# iPod-Video-breakout.net
KiCad netlist of a schematic drawn in EAGLE
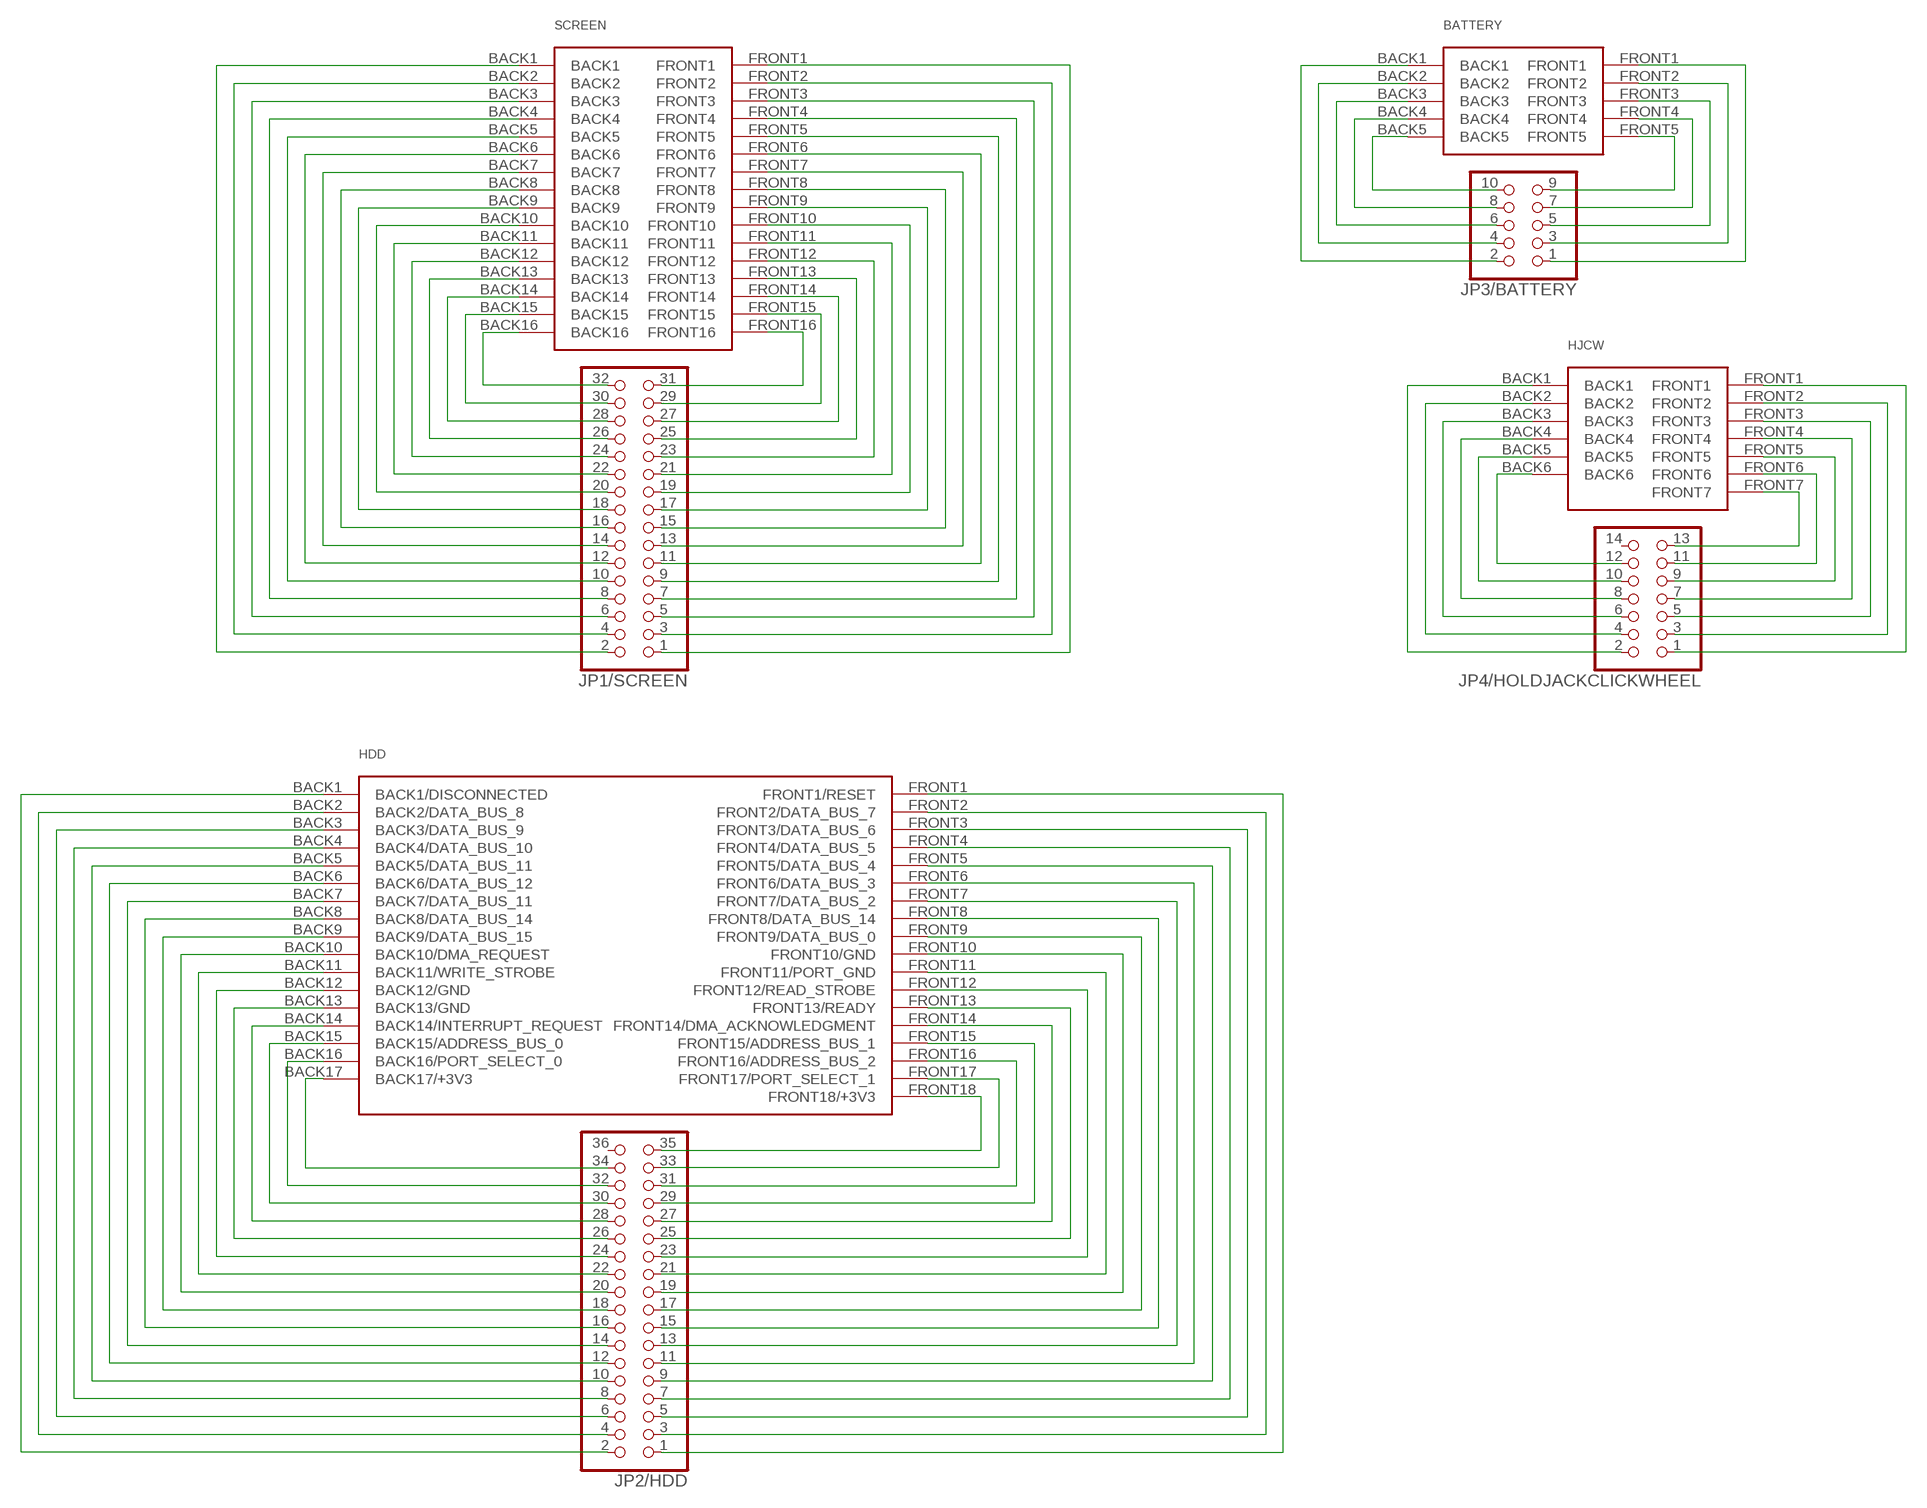
[diagram p0: schematic, sheet 1]

(export (version "E")
  (design (tool "Eeschema 10.0.6"))
  (components
    (comp (ref "BATTERY")
      (value "526100572/BATTERY")
      (footprint "eagle-import:526100572")
      (libsource (lib "eagle-import") (part "526100572/BATTERY"))
    )
    (comp (ref "HDD")
      (value "5035663502/HDD")
      (footprint "eagle-import:5035663502")
      (libsource (lib "eagle-import") (part "5035663502/HDD"))
    )
    (comp (ref "HJCW")
      (value "5035661302/HOLDJACK&CLICKWHEEL")
      (footprint "eagle-import:5035661302")
      (libsource (lib "eagle-import") (part "5035661302/HOLDJACK&CLICKWHEEL"))
    )
    (comp (ref "JP1/SCREEN")
      (value "PINHD-2X16")
      (footprint "eagle-import:2X16")
      (libsource (lib "eagle-import") (part "PINHD-2X16"))
    )
    (comp (ref "JP2/HDD")
      (value "PINHD-2X18")
      (footprint "eagle-import:2X18")
      (libsource (lib "eagle-import") (part "PINHD-2X18"))
    )
    (comp (ref "JP3/BATTERY")
      (value "PINHD-2X5")
      (footprint "eagle-import:2X05")
      (libsource (lib "eagle-import") (part "PINHD-2X5"))
    )
    (comp (ref "JP4/HOLDJACKCLICKWHEEL")
      (value "PINHD-2X7")
      (footprint "eagle-import:2X07")
      (libsource (lib "eagle-import") (part "PINHD-2X7"))
    )
    (comp (ref "SCREEN")
      (value "FF12-32A-R11A/SCREEN")
      (footprint "eagle-import:FF12-32A-R11A")
      (libsource (lib "eagle-import") (part "FF12-32A-R11A/SCREEN"))
    )
  )
  (nets
    (net (code "1") (name "Net-(BATTERY-PadBACK1)") (class "Default")
      (node (ref "BATTERY") (pin "BACK1") (pinfunction "BACK1_BACK1") (pintype "bidirectional"))
      (node (ref "JP3/BATTERY") (pin "2") (pinfunction "2_2") (pintype "passive"))
    )
    (net (code "2") (name "Net-(BATTERY-PadBACK2)") (class "Default")
      (node (ref "BATTERY") (pin "BACK2") (pinfunction "BACK2_BACK2") (pintype "bidirectional"))
      (node (ref "JP3/BATTERY") (pin "4") (pinfunction "4_4") (pintype "passive"))
    )
    (net (code "3") (name "Net-(BATTERY-PadBACK3)") (class "Default")
      (node (ref "BATTERY") (pin "BACK3") (pinfunction "BACK3_BACK3") (pintype "bidirectional"))
      (node (ref "JP3/BATTERY") (pin "6") (pinfunction "6_6") (pintype "passive"))
    )
    (net (code "4") (name "Net-(BATTERY-PadBACK4)") (class "Default")
      (node (ref "BATTERY") (pin "BACK4") (pinfunction "BACK4_BACK4") (pintype "bidirectional"))
      (node (ref "JP3/BATTERY") (pin "8") (pinfunction "8_8") (pintype "passive"))
    )
    (net (code "5") (name "Net-(BATTERY-PadBACK5)") (class "Default")
      (node (ref "BATTERY") (pin "BACK5") (pinfunction "BACK5_BACK5") (pintype "bidirectional"))
      (node (ref "JP3/BATTERY") (pin "10") (pinfunction "10_10") (pintype "passive"))
    )
    (net (code "6") (name "Net-(BATTERY-PadFRONT1)") (class "Default")
      (node (ref "BATTERY") (pin "FRONT1") (pinfunction "FRONT1_FRONT1") (pintype "bidirectional"))
      (node (ref "JP3/BATTERY") (pin "1") (pinfunction "1_1") (pintype "passive"))
    )
    (net (code "7") (name "Net-(BATTERY-PadFRONT2)") (class "Default")
      (node (ref "BATTERY") (pin "FRONT2") (pinfunction "FRONT2_FRONT2") (pintype "bidirectional"))
      (node (ref "JP3/BATTERY") (pin "3") (pinfunction "3_3") (pintype "passive"))
    )
    (net (code "8") (name "Net-(BATTERY-PadFRONT3)") (class "Default")
      (node (ref "BATTERY") (pin "FRONT3") (pinfunction "FRONT3_FRONT3") (pintype "bidirectional"))
      (node (ref "JP3/BATTERY") (pin "5") (pinfunction "5_5") (pintype "passive"))
    )
    (net (code "9") (name "Net-(BATTERY-PadFRONT4)") (class "Default")
      (node (ref "BATTERY") (pin "FRONT4") (pinfunction "FRONT4_FRONT4") (pintype "bidirectional"))
      (node (ref "JP3/BATTERY") (pin "7") (pinfunction "7_7") (pintype "passive"))
    )
    (net (code "10") (name "Net-(BATTERY-PadFRONT5)") (class "Default")
      (node (ref "BATTERY") (pin "FRONT5") (pinfunction "FRONT5_FRONT5") (pintype "bidirectional"))
      (node (ref "JP3/BATTERY") (pin "9") (pinfunction "9_9") (pintype "passive"))
    )
    (net (code "11") (name "Net-(HDD-BACK1{slash}DISCONNECTED)") (class "Default")
      (node (ref "HDD") (pin "BACK1") (pinfunction "BACK1/DISCONNECTED_BACK1") (pintype "bidirectional"))
      (node (ref "JP2/HDD") (pin "2") (pinfunction "2_2") (pintype "passive"))
    )
    (net (code "12") (name "Net-(HDD-BACK2{slash}DATA_BUS_8)") (class "Default")
      (node (ref "HDD") (pin "BACK2") (pinfunction "BACK2/DATA_BUS_8_BACK2") (pintype "bidirectional"))
      (node (ref "JP2/HDD") (pin "4") (pinfunction "4_4") (pintype "passive"))
    )
    (net (code "13") (name "Net-(HDD-BACK3{slash}DATA_BUS_9)") (class "Default")
      (node (ref "HDD") (pin "BACK3") (pinfunction "BACK3/DATA_BUS_9_BACK3") (pintype "bidirectional"))
      (node (ref "JP2/HDD") (pin "6") (pinfunction "6_6") (pintype "passive"))
    )
    (net (code "14") (name "Net-(HDD-BACK4{slash}DATA_BUS_10)") (class "Default")
      (node (ref "HDD") (pin "BACK4") (pinfunction "BACK4/DATA_BUS_10_BACK4") (pintype "bidirectional"))
      (node (ref "JP2/HDD") (pin "8") (pinfunction "8_8") (pintype "passive"))
    )
    (net (code "15") (name "Net-(HDD-BACK5{slash}DATA_BUS_11)") (class "Default")
      (node (ref "HDD") (pin "BACK5") (pinfunction "BACK5/DATA_BUS_11_BACK5") (pintype "bidirectional"))
      (node (ref "JP2/HDD") (pin "10") (pinfunction "10_10") (pintype "passive"))
    )
    (net (code "16") (name "Net-(HDD-BACK6{slash}DATA_BUS_12)") (class "Default")
      (node (ref "HDD") (pin "BACK6") (pinfunction "BACK6/DATA_BUS_12_BACK6") (pintype "bidirectional"))
      (node (ref "JP2/HDD") (pin "12") (pinfunction "12_12") (pintype "passive"))
    )
    (net (code "17") (name "Net-(HDD-BACK7{slash}DATA_BUS_11)") (class "Default")
      (node (ref "HDD") (pin "BACK7") (pinfunction "BACK7/DATA_BUS_11_BACK7") (pintype "bidirectional"))
      (node (ref "JP2/HDD") (pin "14") (pinfunction "14_14") (pintype "passive"))
    )
    (net (code "18") (name "Net-(HDD-BACK8{slash}DATA_BUS_14)") (class "Default")
      (node (ref "HDD") (pin "BACK8") (pinfunction "BACK8/DATA_BUS_14_BACK8") (pintype "bidirectional"))
      (node (ref "JP2/HDD") (pin "16") (pinfunction "16_16") (pintype "passive"))
    )
    (net (code "19") (name "Net-(HDD-BACK9{slash}DATA_BUS_15)") (class "Default")
      (node (ref "HDD") (pin "BACK9") (pinfunction "BACK9/DATA_BUS_15_BACK9") (pintype "bidirectional"))
      (node (ref "JP2/HDD") (pin "18") (pinfunction "18_18") (pintype "passive"))
    )
    (net (code "20") (name "Net-(HDD-BACK10{slash}DMA_REQUEST)") (class "Default")
      (node (ref "HDD") (pin "BACK10") (pinfunction "BACK10/DMA_REQUEST_BACK10") (pintype "bidirectional"))
      (node (ref "JP2/HDD") (pin "20") (pinfunction "20_20") (pintype "passive"))
    )
    (net (code "21") (name "Net-(HDD-BACK11{slash}WRITE_STROBE)") (class "Default")
      (node (ref "HDD") (pin "BACK11") (pinfunction "BACK11/WRITE_STROBE_BACK11") (pintype "bidirectional"))
      (node (ref "JP2/HDD") (pin "22") (pinfunction "22_22") (pintype "passive"))
    )
    (net (code "22") (name "Net-(HDD-BACK12{slash}GND)") (class "Default")
      (node (ref "HDD") (pin "BACK12") (pinfunction "BACK12/GND_BACK12") (pintype "bidirectional"))
      (node (ref "JP2/HDD") (pin "24") (pinfunction "24_24") (pintype "passive"))
    )
    (net (code "23") (name "Net-(HDD-BACK13{slash}GND)") (class "Default")
      (node (ref "HDD") (pin "BACK13") (pinfunction "BACK13/GND_BACK13") (pintype "bidirectional"))
      (node (ref "JP2/HDD") (pin "26") (pinfunction "26_26") (pintype "passive"))
    )
    (net (code "24") (name "Net-(HDD-BACK14{slash}INTERRUPT_REQUEST)") (class "Default")
      (node (ref "HDD") (pin "BACK14") (pinfunction "BACK14/INTERRUPT_REQUEST_BACK14") (pintype "bidirectional"))
      (node (ref "JP2/HDD") (pin "28") (pinfunction "28_28") (pintype "passive"))
    )
    (net (code "25") (name "Net-(HDD-BACK15{slash}ADDRESS_BUS_0)") (class "Default")
      (node (ref "HDD") (pin "BACK15") (pinfunction "BACK15/ADDRESS_BUS_0_BACK15") (pintype "bidirectional"))
      (node (ref "JP2/HDD") (pin "30") (pinfunction "30_30") (pintype "passive"))
    )
    (net (code "26") (name "Net-(HDD-BACK16{slash}PORT_SELECT_0)") (class "Default")
      (node (ref "HDD") (pin "BACK16") (pinfunction "BACK16/PORT_SELECT_0_BACK16") (pintype "bidirectional"))
      (node (ref "JP2/HDD") (pin "32") (pinfunction "32_32") (pintype "passive"))
    )
    (net (code "27") (name "Net-(HDD-BACK17{slash}+3V3)") (class "Default")
      (node (ref "HDD") (pin "BACK17") (pinfunction "BACK17/+3V3_BACK17") (pintype "bidirectional"))
      (node (ref "JP2/HDD") (pin "34") (pinfunction "34_34") (pintype "passive"))
    )
    (net (code "28") (name "Net-(HDD-FRONT1{slash}RESET)") (class "Default")
      (node (ref "HDD") (pin "FRONT1") (pinfunction "FRONT1/RESET_FRONT1") (pintype "bidirectional"))
      (node (ref "JP2/HDD") (pin "1") (pinfunction "1_1") (pintype "passive"))
    )
    (net (code "29") (name "Net-(HDD-FRONT2{slash}DATA_BUS_7)") (class "Default")
      (node (ref "HDD") (pin "FRONT2") (pinfunction "FRONT2/DATA_BUS_7_FRONT2") (pintype "bidirectional"))
      (node (ref "JP2/HDD") (pin "3") (pinfunction "3_3") (pintype "passive"))
    )
    (net (code "30") (name "Net-(HDD-FRONT3{slash}DATA_BUS_6)") (class "Default")
      (node (ref "HDD") (pin "FRONT3") (pinfunction "FRONT3/DATA_BUS_6_FRONT3") (pintype "bidirectional"))
      (node (ref "JP2/HDD") (pin "5") (pinfunction "5_5") (pintype "passive"))
    )
    (net (code "31") (name "Net-(HDD-FRONT4{slash}DATA_BUS_5)") (class "Default")
      (node (ref "HDD") (pin "FRONT4") (pinfunction "FRONT4/DATA_BUS_5_FRONT4") (pintype "bidirectional"))
      (node (ref "JP2/HDD") (pin "7") (pinfunction "7_7") (pintype "passive"))
    )
    (net (code "32") (name "Net-(HDD-FRONT5{slash}DATA_BUS_4)") (class "Default")
      (node (ref "HDD") (pin "FRONT5") (pinfunction "FRONT5/DATA_BUS_4_FRONT5") (pintype "bidirectional"))
      (node (ref "JP2/HDD") (pin "9") (pinfunction "9_9") (pintype "passive"))
    )
    (net (code "33") (name "Net-(HDD-FRONT6{slash}DATA_BUS_3)") (class "Default")
      (node (ref "HDD") (pin "FRONT6") (pinfunction "FRONT6/DATA_BUS_3_FRONT6") (pintype "bidirectional"))
      (node (ref "JP2/HDD") (pin "11") (pinfunction "11_11") (pintype "passive"))
    )
    (net (code "34") (name "Net-(HDD-FRONT7{slash}DATA_BUS_2)") (class "Default")
      (node (ref "HDD") (pin "FRONT7") (pinfunction "FRONT7/DATA_BUS_2_FRONT7") (pintype "bidirectional"))
      (node (ref "JP2/HDD") (pin "13") (pinfunction "13_13") (pintype "passive"))
    )
    (net (code "35") (name "Net-(HDD-FRONT8{slash}DATA_BUS_14)") (class "Default")
      (node (ref "HDD") (pin "FRONT8") (pinfunction "FRONT8/DATA_BUS_14_FRONT8") (pintype "bidirectional"))
      (node (ref "JP2/HDD") (pin "15") (pinfunction "15_15") (pintype "passive"))
    )
    (net (code "36") (name "Net-(HDD-FRONT9{slash}DATA_BUS_0)") (class "Default")
      (node (ref "HDD") (pin "FRONT9") (pinfunction "FRONT9/DATA_BUS_0_FRONT9") (pintype "bidirectional"))
      (node (ref "JP2/HDD") (pin "17") (pinfunction "17_17") (pintype "passive"))
    )
    (net (code "37") (name "Net-(HDD-FRONT10{slash}GND)") (class "Default")
      (node (ref "HDD") (pin "FRONT10") (pinfunction "FRONT10/GND_FRONT10") (pintype "bidirectional"))
      (node (ref "JP2/HDD") (pin "19") (pinfunction "19_19") (pintype "passive"))
    )
    (net (code "38") (name "Net-(HDD-FRONT11{slash}PORT_GND)") (class "Default")
      (node (ref "HDD") (pin "FRONT11") (pinfunction "FRONT11/PORT_GND_FRONT11") (pintype "bidirectional"))
      (node (ref "JP2/HDD") (pin "21") (pinfunction "21_21") (pintype "passive"))
    )
    (net (code "39") (name "Net-(HDD-FRONT12{slash}READ_STROBE)") (class "Default")
      (node (ref "HDD") (pin "FRONT12") (pinfunction "FRONT12/READ_STROBE_FRONT12") (pintype "bidirectional"))
      (node (ref "JP2/HDD") (pin "23") (pinfunction "23_23") (pintype "passive"))
    )
    (net (code "40") (name "Net-(HDD-FRONT13{slash}READY)") (class "Default")
      (node (ref "HDD") (pin "FRONT13") (pinfunction "FRONT13/READY_FRONT13") (pintype "bidirectional"))
      (node (ref "JP2/HDD") (pin "25") (pinfunction "25_25") (pintype "passive"))
    )
    (net (code "41") (name "Net-(HDD-FRONT14{slash}DMA_ACKNOWLEDGMENT)") (class "Default")
      (node (ref "HDD") (pin "FRONT14") (pinfunction "FRONT14/DMA_ACKNOWLEDGMENT_FRONT14") (pintype "bidirectional"))
      (node (ref "JP2/HDD") (pin "27") (pinfunction "27_27") (pintype "passive"))
    )
    (net (code "42") (name "Net-(HDD-FRONT15{slash}ADDRESS_BUS_1)") (class "Default")
      (node (ref "HDD") (pin "FRONT15") (pinfunction "FRONT15/ADDRESS_BUS_1_FRONT15") (pintype "bidirectional"))
      (node (ref "JP2/HDD") (pin "29") (pinfunction "29_29") (pintype "passive"))
    )
    (net (code "43") (name "Net-(HDD-FRONT16{slash}ADDRESS_BUS_2)") (class "Default")
      (node (ref "HDD") (pin "FRONT16") (pinfunction "FRONT16/ADDRESS_BUS_2_FRONT16") (pintype "bidirectional"))
      (node (ref "JP2/HDD") (pin "31") (pinfunction "31_31") (pintype "passive"))
    )
    (net (code "44") (name "Net-(HDD-FRONT17{slash}PORT_SELECT_1)") (class "Default")
      (node (ref "HDD") (pin "FRONT17") (pinfunction "FRONT17/PORT_SELECT_1_FRONT17") (pintype "bidirectional"))
      (node (ref "JP2/HDD") (pin "33") (pinfunction "33_33") (pintype "passive"))
    )
    (net (code "45") (name "Net-(HDD-FRONT18{slash}+3V3)") (class "Default")
      (node (ref "HDD") (pin "FRONT18") (pinfunction "FRONT18/+3V3_FRONT18") (pintype "bidirectional"))
      (node (ref "JP2/HDD") (pin "35") (pinfunction "35_35") (pintype "passive"))
    )
    (net (code "46") (name "Net-(HJCW-PadBACK1)") (class "Default")
      (node (ref "HJCW") (pin "BACK1") (pinfunction "BACK1_BACK1") (pintype "bidirectional"))
      (node (ref "JP4/HOLDJACKCLICKWHEEL") (pin "2") (pinfunction "2_2") (pintype "passive"))
    )
    (net (code "47") (name "Net-(HJCW-PadBACK2)") (class "Default")
      (node (ref "HJCW") (pin "BACK2") (pinfunction "BACK2_BACK2") (pintype "bidirectional"))
      (node (ref "JP4/HOLDJACKCLICKWHEEL") (pin "4") (pinfunction "4_4") (pintype "passive"))
    )
    (net (code "48") (name "Net-(HJCW-PadBACK3)") (class "Default")
      (node (ref "HJCW") (pin "BACK3") (pinfunction "BACK3_BACK3") (pintype "bidirectional"))
      (node (ref "JP4/HOLDJACKCLICKWHEEL") (pin "6") (pinfunction "6_6") (pintype "passive"))
    )
    (net (code "49") (name "Net-(HJCW-PadBACK4)") (class "Default")
      (node (ref "HJCW") (pin "BACK4") (pinfunction "BACK4_BACK4") (pintype "bidirectional"))
      (node (ref "JP4/HOLDJACKCLICKWHEEL") (pin "8") (pinfunction "8_8") (pintype "passive"))
    )
    (net (code "50") (name "Net-(HJCW-PadBACK5)") (class "Default")
      (node (ref "HJCW") (pin "BACK5") (pinfunction "BACK5_BACK5") (pintype "bidirectional"))
      (node (ref "JP4/HOLDJACKCLICKWHEEL") (pin "10") (pinfunction "10_10") (pintype "passive"))
    )
    (net (code "51") (name "Net-(HJCW-PadBACK6)") (class "Default")
      (node (ref "HJCW") (pin "BACK6") (pinfunction "BACK6_BACK6") (pintype "bidirectional"))
      (node (ref "JP4/HOLDJACKCLICKWHEEL") (pin "12") (pinfunction "12_12") (pintype "passive"))
    )
    (net (code "52") (name "Net-(HJCW-PadFRONT1)") (class "Default")
      (node (ref "HJCW") (pin "FRONT1") (pinfunction "FRONT1_FRONT1") (pintype "bidirectional"))
      (node (ref "JP4/HOLDJACKCLICKWHEEL") (pin "1") (pinfunction "1_1") (pintype "passive"))
    )
    (net (code "53") (name "Net-(HJCW-PadFRONT2)") (class "Default")
      (node (ref "HJCW") (pin "FRONT2") (pinfunction "FRONT2_FRONT2") (pintype "bidirectional"))
      (node (ref "JP4/HOLDJACKCLICKWHEEL") (pin "3") (pinfunction "3_3") (pintype "passive"))
    )
    (net (code "54") (name "Net-(HJCW-PadFRONT3)") (class "Default")
      (node (ref "HJCW") (pin "FRONT3") (pinfunction "FRONT3_FRONT3") (pintype "bidirectional"))
      (node (ref "JP4/HOLDJACKCLICKWHEEL") (pin "5") (pinfunction "5_5") (pintype "passive"))
    )
    (net (code "55") (name "Net-(HJCW-PadFRONT4)") (class "Default")
      (node (ref "HJCW") (pin "FRONT4") (pinfunction "FRONT4_FRONT4") (pintype "bidirectional"))
      (node (ref "JP4/HOLDJACKCLICKWHEEL") (pin "7") (pinfunction "7_7") (pintype "passive"))
    )
    (net (code "56") (name "Net-(HJCW-PadFRONT5)") (class "Default")
      (node (ref "HJCW") (pin "FRONT5") (pinfunction "FRONT5_FRONT5") (pintype "bidirectional"))
      (node (ref "JP4/HOLDJACKCLICKWHEEL") (pin "9") (pinfunction "9_9") (pintype "passive"))
    )
    (net (code "57") (name "Net-(HJCW-PadFRONT6)") (class "Default")
      (node (ref "HJCW") (pin "FRONT6") (pinfunction "FRONT6_FRONT6") (pintype "bidirectional"))
      (node (ref "JP4/HOLDJACKCLICKWHEEL") (pin "11") (pinfunction "11_11") (pintype "passive"))
    )
    (net (code "58") (name "Net-(HJCW-PadFRONT7)") (class "Default")
      (node (ref "HJCW") (pin "FRONT7") (pinfunction "FRONT7_FRONT7") (pintype "bidirectional"))
      (node (ref "JP4/HOLDJACKCLICKWHEEL") (pin "13") (pinfunction "13_13") (pintype "passive"))
    )
    (net (code "59") (name "Net-(JP1/SCREEN-Pad1)") (class "Default")
      (node (ref "JP1/SCREEN") (pin "1") (pinfunction "1_1") (pintype "passive"))
      (node (ref "SCREEN") (pin "FRONT1") (pinfunction "FRONT1_FRONT1") (pintype "bidirectional"))
    )
    (net (code "60") (name "Net-(JP1/SCREEN-Pad2)") (class "Default")
      (node (ref "JP1/SCREEN") (pin "2") (pinfunction "2_2") (pintype "passive"))
      (node (ref "SCREEN") (pin "BACK1") (pinfunction "BACK1_BACK1") (pintype "bidirectional"))
    )
    (net (code "61") (name "Net-(JP1/SCREEN-Pad3)") (class "Default")
      (node (ref "JP1/SCREEN") (pin "3") (pinfunction "3_3") (pintype "passive"))
      (node (ref "SCREEN") (pin "FRONT2") (pinfunction "FRONT2_FRONT2") (pintype "bidirectional"))
    )
    (net (code "62") (name "Net-(JP1/SCREEN-Pad4)") (class "Default")
      (node (ref "JP1/SCREEN") (pin "4") (pinfunction "4_4") (pintype "passive"))
      (node (ref "SCREEN") (pin "BACK2") (pinfunction "BACK2_BACK2") (pintype "bidirectional"))
    )
    (net (code "63") (name "Net-(JP1/SCREEN-Pad5)") (class "Default")
      (node (ref "JP1/SCREEN") (pin "5") (pinfunction "5_5") (pintype "passive"))
      (node (ref "SCREEN") (pin "FRONT3") (pinfunction "FRONT3_FRONT3") (pintype "bidirectional"))
    )
    (net (code "64") (name "Net-(JP1/SCREEN-Pad6)") (class "Default")
      (node (ref "JP1/SCREEN") (pin "6") (pinfunction "6_6") (pintype "passive"))
      (node (ref "SCREEN") (pin "BACK3") (pinfunction "BACK3_BACK3") (pintype "bidirectional"))
    )
    (net (code "65") (name "Net-(JP1/SCREEN-Pad7)") (class "Default")
      (node (ref "JP1/SCREEN") (pin "7") (pinfunction "7_7") (pintype "passive"))
      (node (ref "SCREEN") (pin "FRONT4") (pinfunction "FRONT4_FRONT4") (pintype "bidirectional"))
    )
    (net (code "66") (name "Net-(JP1/SCREEN-Pad8)") (class "Default")
      (node (ref "JP1/SCREEN") (pin "8") (pinfunction "8_8") (pintype "passive"))
      (node (ref "SCREEN") (pin "BACK4") (pinfunction "BACK4_BACK4") (pintype "bidirectional"))
    )
    (net (code "67") (name "Net-(JP1/SCREEN-Pad9)") (class "Default")
      (node (ref "JP1/SCREEN") (pin "9") (pinfunction "9_9") (pintype "passive"))
      (node (ref "SCREEN") (pin "FRONT5") (pinfunction "FRONT5_FRONT5") (pintype "bidirectional"))
    )
    (net (code "68") (name "Net-(JP1/SCREEN-Pad10)") (class "Default")
      (node (ref "JP1/SCREEN") (pin "10") (pinfunction "10_10") (pintype "passive"))
      (node (ref "SCREEN") (pin "BACK5") (pinfunction "BACK5_BACK5") (pintype "bidirectional"))
    )
    (net (code "69") (name "Net-(JP1/SCREEN-Pad11)") (class "Default")
      (node (ref "JP1/SCREEN") (pin "11") (pinfunction "11_11") (pintype "passive"))
      (node (ref "SCREEN") (pin "FRONT6") (pinfunction "FRONT6_FRONT6") (pintype "bidirectional"))
    )
    (net (code "70") (name "Net-(JP1/SCREEN-Pad12)") (class "Default")
      (node (ref "JP1/SCREEN") (pin "12") (pinfunction "12_12") (pintype "passive"))
      (node (ref "SCREEN") (pin "BACK6") (pinfunction "BACK6_BACK6") (pintype "bidirectional"))
    )
    (net (code "71") (name "Net-(JP1/SCREEN-Pad13)") (class "Default")
      (node (ref "JP1/SCREEN") (pin "13") (pinfunction "13_13") (pintype "passive"))
      (node (ref "SCREEN") (pin "FRONT7") (pinfunction "FRONT7_FRONT7") (pintype "bidirectional"))
    )
    (net (code "72") (name "Net-(JP1/SCREEN-Pad14)") (class "Default")
      (node (ref "JP1/SCREEN") (pin "14") (pinfunction "14_14") (pintype "passive"))
      (node (ref "SCREEN") (pin "BACK7") (pinfunction "BACK7_BACK7") (pintype "bidirectional"))
    )
    (net (code "73") (name "Net-(JP1/SCREEN-Pad15)") (class "Default")
      (node (ref "JP1/SCREEN") (pin "15") (pinfunction "15_15") (pintype "passive"))
      (node (ref "SCREEN") (pin "FRONT8") (pinfunction "FRONT8_FRONT8") (pintype "bidirectional"))
    )
    (net (code "74") (name "Net-(JP1/SCREEN-Pad16)") (class "Default")
      (node (ref "JP1/SCREEN") (pin "16") (pinfunction "16_16") (pintype "passive"))
      (node (ref "SCREEN") (pin "BACK8") (pinfunction "BACK8_BACK8") (pintype "bidirectional"))
    )
    (net (code "75") (name "Net-(JP1/SCREEN-Pad17)") (class "Default")
      (node (ref "JP1/SCREEN") (pin "17") (pinfunction "17_17") (pintype "passive"))
      (node (ref "SCREEN") (pin "FRONT9") (pinfunction "FRONT9_FRONT9") (pintype "bidirectional"))
    )
    (net (code "76") (name "Net-(JP1/SCREEN-Pad18)") (class "Default")
      (node (ref "JP1/SCREEN") (pin "18") (pinfunction "18_18") (pintype "passive"))
      (node (ref "SCREEN") (pin "BACK9") (pinfunction "BACK9_BACK9") (pintype "bidirectional"))
    )
    (net (code "77") (name "Net-(JP1/SCREEN-Pad19)") (class "Default")
      (node (ref "JP1/SCREEN") (pin "19") (pinfunction "19_19") (pintype "passive"))
      (node (ref "SCREEN") (pin "FRONT10") (pinfunction "FRONT10_FRONT10") (pintype "bidirectional"))
    )
    (net (code "78") (name "Net-(JP1/SCREEN-Pad20)") (class "Default")
      (node (ref "JP1/SCREEN") (pin "20") (pinfunction "20_20") (pintype "passive"))
      (node (ref "SCREEN") (pin "BACK10") (pinfunction "BACK10_BACK10") (pintype "bidirectional"))
    )
    (net (code "79") (name "Net-(JP1/SCREEN-Pad21)") (class "Default")
      (node (ref "JP1/SCREEN") (pin "21") (pinfunction "21_21") (pintype "passive"))
      (node (ref "SCREEN") (pin "FRONT11") (pinfunction "FRONT11_FRONT11") (pintype "bidirectional"))
    )
    (net (code "80") (name "Net-(JP1/SCREEN-Pad22)") (class "Default")
      (node (ref "JP1/SCREEN") (pin "22") (pinfunction "22_22") (pintype "passive"))
      (node (ref "SCREEN") (pin "BACK11") (pinfunction "BACK11_BACK11") (pintype "bidirectional"))
    )
    (net (code "81") (name "Net-(JP1/SCREEN-Pad23)") (class "Default")
      (node (ref "JP1/SCREEN") (pin "23") (pinfunction "23_23") (pintype "passive"))
      (node (ref "SCREEN") (pin "FRONT12") (pinfunction "FRONT12_FRONT12") (pintype "bidirectional"))
    )
    (net (code "82") (name "Net-(JP1/SCREEN-Pad24)") (class "Default")
      (node (ref "JP1/SCREEN") (pin "24") (pinfunction "24_24") (pintype "passive"))
      (node (ref "SCREEN") (pin "BACK12") (pinfunction "BACK12_BACK12") (pintype "bidirectional"))
    )
    (net (code "83") (name "Net-(JP1/SCREEN-Pad25)") (class "Default")
      (node (ref "JP1/SCREEN") (pin "25") (pinfunction "25_25") (pintype "passive"))
      (node (ref "SCREEN") (pin "FRONT13") (pinfunction "FRONT13_FRONT13") (pintype "bidirectional"))
    )
    (net (code "84") (name "Net-(JP1/SCREEN-Pad26)") (class "Default")
      (node (ref "JP1/SCREEN") (pin "26") (pinfunction "26_26") (pintype "passive"))
      (node (ref "SCREEN") (pin "BACK13") (pinfunction "BACK13_BACK13") (pintype "bidirectional"))
    )
    (net (code "85") (name "Net-(JP1/SCREEN-Pad27)") (class "Default")
      (node (ref "JP1/SCREEN") (pin "27") (pinfunction "27_27") (pintype "passive"))
      (node (ref "SCREEN") (pin "FRONT14") (pinfunction "FRONT14_FRONT14") (pintype "bidirectional"))
    )
    (net (code "86") (name "Net-(JP1/SCREEN-Pad28)") (class "Default")
      (node (ref "JP1/SCREEN") (pin "28") (pinfunction "28_28") (pintype "passive"))
      (node (ref "SCREEN") (pin "BACK14") (pinfunction "BACK14_BACK14") (pintype "bidirectional"))
    )
    (net (code "87") (name "Net-(JP1/SCREEN-Pad29)") (class "Default")
      (node (ref "JP1/SCREEN") (pin "29") (pinfunction "29_29") (pintype "passive"))
      (node (ref "SCREEN") (pin "FRONT15") (pinfunction "FRONT15_FRONT15") (pintype "bidirectional"))
    )
    (net (code "88") (name "Net-(JP1/SCREEN-Pad30)") (class "Default")
      (node (ref "JP1/SCREEN") (pin "30") (pinfunction "30_30") (pintype "passive"))
      (node (ref "SCREEN") (pin "BACK15") (pinfunction "BACK15_BACK15") (pintype "bidirectional"))
    )
    (net (code "89") (name "Net-(JP1/SCREEN-Pad31)") (class "Default")
      (node (ref "JP1/SCREEN") (pin "31") (pinfunction "31_31") (pintype "passive"))
      (node (ref "SCREEN") (pin "FRONT16") (pinfunction "FRONT16_FRONT16") (pintype "bidirectional"))
    )
    (net (code "90") (name "Net-(JP1/SCREEN-Pad32)") (class "Default")
      (node (ref "JP1/SCREEN") (pin "32") (pinfunction "32_32") (pintype "passive"))
      (node (ref "SCREEN") (pin "BACK16") (pinfunction "BACK16_BACK16") (pintype "bidirectional"))
    )
    (net (code "91") (name "unconnected-(JP2/HDD-Pad36)") (class "Default")
      (node (ref "JP2/HDD") (pin "36") (pinfunction "36_36") (pintype "passive"))
    )
    (net (code "92") (name "unconnected-(JP4/HOLDJACKCLICKWHEEL-Pad14)") (class "Default")
      (node (ref "JP4/HOLDJACKCLICKWHEEL") (pin "14") (pinfunction "14_14") (pintype "passive"))
    )
  )
)
